# TestPoints.net
KiCad netlist of a schematic drawn in Altium Designer
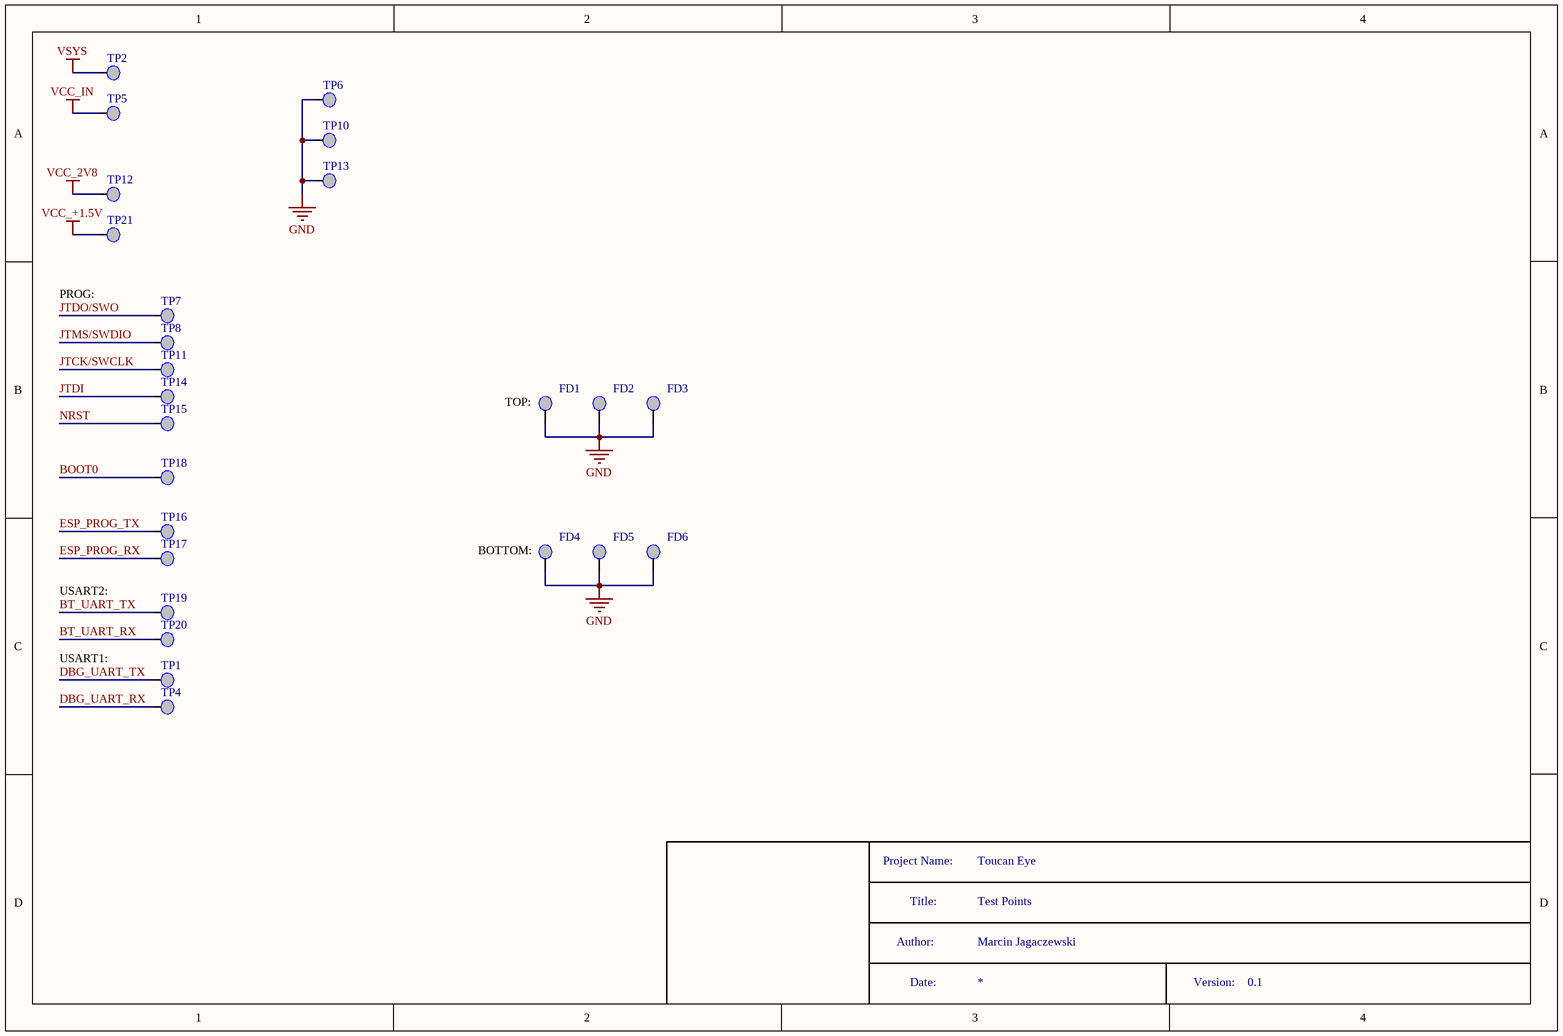
[diagram p0: TestPoints.SchDoc]

(export (version "E")
  (design (tool "Eeschema 10.0.6"))
  (components
    (comp (ref "FD1") (value "Fiducial") (footprint "Fiducial") (libsource (lib "CONN") (part "Fiducial")))
    (comp (ref "FD2") (value "Fiducial") (footprint "Fiducial") (libsource (lib "CONN") (part "Fiducial")))
    (comp (ref "FD3") (value "Fiducial") (footprint "Fiducial") (libsource (lib "CONN") (part "Fiducial")))
    (comp (ref "FD4") (value "Fiducial") (footprint "Fiducial") (libsource (lib "CONN") (part "Fiducial")))
    (comp (ref "FD5") (value "Fiducial") (footprint "Fiducial") (libsource (lib "CONN") (part "Fiducial")))
    (comp (ref "FD6") (value "Fiducial") (footprint "Fiducial") (libsource (lib "CONN") (part "Fiducial")))
    (comp (ref "TP1") (value "Test_Point") (footprint "TP") (libsource (lib "Holes") (part "Test_Point")))
    (comp (ref "TP2") (value "Test_Point") (footprint "TP") (libsource (lib "Holes") (part "Test_Point")))
    (comp (ref "TP4") (value "Test_Point") (footprint "TP") (libsource (lib "Holes") (part "Test_Point")))
    (comp (ref "TP5") (value "Test_Point") (footprint "TP") (libsource (lib "Holes") (part "Test_Point")))
    (comp (ref "TP6") (value "Test_Point") (footprint "TP") (libsource (lib "Holes") (part "Test_Point")))
    (comp (ref "TP7") (value "Test_Point") (footprint "TP") (libsource (lib "Holes") (part "Test_Point")))
    (comp (ref "TP8") (value "Test_Point") (footprint "TP") (libsource (lib "Holes") (part "Test_Point")))
    (comp (ref "TP10") (value "Test_Point") (footprint "TP") (libsource (lib "Holes") (part "Test_Point")))
    (comp (ref "TP11") (value "Test_Point") (footprint "TP") (libsource (lib "Holes") (part "Test_Point")))
    (comp (ref "TP12") (value "Test_Point") (footprint "TP") (libsource (lib "Holes") (part "Test_Point")))
    (comp (ref "TP13") (value "Test_Point") (footprint "TP") (libsource (lib "Holes") (part "Test_Point")))
    (comp (ref "TP14") (value "Test_Point") (footprint "TP") (libsource (lib "Holes") (part "Test_Point")))
    (comp (ref "TP15") (value "Test_Point") (footprint "TP") (libsource (lib "Holes") (part "Test_Point")))
    (comp (ref "TP16") (value "Test_Point") (footprint "TP") (libsource (lib "Holes") (part "Test_Point")))
    (comp (ref "TP17") (value "Test_Point") (footprint "TP") (libsource (lib "Holes") (part "Test_Point")))
    (comp (ref "TP18") (value "Test_Point") (footprint "TP") (libsource (lib "Holes") (part "Test_Point")))
    (comp (ref "TP19") (value "Test_Point") (footprint "TP") (libsource (lib "Holes") (part "Test_Point")))
    (comp (ref "TP20") (value "Test_Point") (footprint "TP") (libsource (lib "Holes") (part "Test_Point")))
    (comp (ref "TP21") (value "Test_Point") (footprint "TP") (libsource (lib "Holes") (part "Test_Point")))
  )
  (nets
    (net (code "1") (name "/BOOT0") (class "Default")
      (node (ref "TP18") (pin "1") (pinfunction "TP_1") (pintype "power_in"))
    )
    (net (code "2") (name "/BT_UART_RX") (class "Default")
      (node (ref "TP20") (pin "1") (pinfunction "TP_1") (pintype "power_in"))
    )
    (net (code "3") (name "/BT_UART_TX") (class "Default")
      (node (ref "TP19") (pin "1") (pinfunction "TP_1") (pintype "power_in"))
    )
    (net (code "4") (name "/DBG_UART_RX") (class "Default")
      (node (ref "TP4") (pin "1") (pinfunction "TP_1") (pintype "power_in"))
    )
    (net (code "5") (name "/DBG_UART_TX") (class "Default")
      (node (ref "TP1") (pin "1") (pinfunction "TP_1") (pintype "power_in"))
    )
    (net (code "6") (name "/ESP_PROG_RX") (class "Default")
      (node (ref "TP17") (pin "1") (pinfunction "TP_1") (pintype "power_in"))
    )
    (net (code "7") (name "/ESP_PROG_TX") (class "Default")
      (node (ref "TP16") (pin "1") (pinfunction "TP_1") (pintype "power_in"))
    )
    (net (code "8") (name "/JTCK{slash}SWCLK") (class "Default")
      (node (ref "TP11") (pin "1") (pinfunction "TP_1") (pintype "power_in"))
    )
    (net (code "9") (name "/JTDI") (class "Default")
      (node (ref "TP14") (pin "1") (pinfunction "TP_1") (pintype "power_in"))
    )
    (net (code "10") (name "/JTDO{slash}SWO") (class "Default")
      (node (ref "TP7") (pin "1") (pinfunction "TP_1") (pintype "power_in"))
    )
    (net (code "11") (name "/JTMS{slash}SWDIO") (class "Default")
      (node (ref "TP8") (pin "1") (pinfunction "TP_1") (pintype "power_in"))
    )
    (net (code "12") (name "/NRST") (class "Default")
      (node (ref "TP15") (pin "1") (pinfunction "TP_1") (pintype "power_in"))
    )
    (net (code "13") (name "GND") (class "Default")
      (node (ref "FD1") (pin "1") (pinfunction "GND_1") (pintype "power_in"))
      (node (ref "FD2") (pin "1") (pinfunction "GND_1") (pintype "power_in"))
      (node (ref "FD3") (pin "1") (pinfunction "GND_1") (pintype "power_in"))
      (node (ref "FD4") (pin "1") (pinfunction "GND_1") (pintype "power_in"))
      (node (ref "FD5") (pin "1") (pinfunction "GND_1") (pintype "power_in"))
      (node (ref "FD6") (pin "1") (pinfunction "GND_1") (pintype "power_in"))
      (node (ref "TP10") (pin "1") (pinfunction "TP_1") (pintype "power_in"))
      (node (ref "TP13") (pin "1") (pinfunction "TP_1") (pintype "power_in"))
      (node (ref "TP6") (pin "1") (pinfunction "TP_1") (pintype "power_in"))
    )
    (net (code "14") (name "VCC_+1.5V") (class "Default")
      (node (ref "TP21") (pin "1") (pinfunction "TP_1") (pintype "power_in"))
    )
    (net (code "15") (name "VCC_2V8") (class "Default")
      (node (ref "TP12") (pin "1") (pinfunction "TP_1") (pintype "power_in"))
    )
    (net (code "16") (name "VCC_IN") (class "Default")
      (node (ref "TP5") (pin "1") (pinfunction "TP_1") (pintype "power_in"))
    )
    (net (code "17") (name "VSYS") (class "Default")
      (node (ref "TP2") (pin "1") (pinfunction "TP_1") (pintype "power_in"))
    )
  )
)
